# LED_adapt.net
KiCad netlist of a schematic drawn in Altium Designer
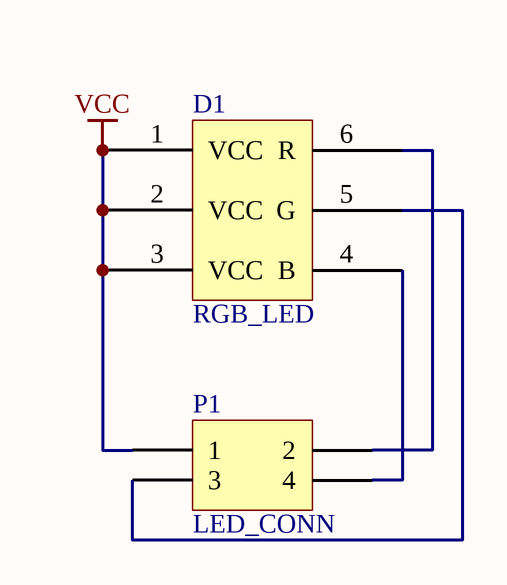
[diagram p0: LED_adapt.SchDoc]

(export (version "E")
  (design (tool "Eeschema 10.0.6"))
  (components
    (comp (ref "D1") (value "RGB_LED") (footprint "CREE_LED") (libsource (lib "mrone") (part "CREE_LED")))
    (comp (ref "P1")
      (value "LED_CONN")
      (footprint "HDR2X2")
      (description "Header, 2-Pin, Dual row")
      (fields (field (name "PUBLISHER") "Altium Limited"))
      (libsource (lib "Miscellaneous Connectors") (part "Header 2X2"))
    )
  )
  (nets
    (net (code "1") (name "Net-(D1-B)") (class "Default")
      (node (ref "D1") (pin "4") (pinfunction "B_4") (pintype "passive"))
      (node (ref "P1") (pin "4") (pinfunction "4_4") (pintype "passive"))
    )
    (net (code "2") (name "Net-(D1-G)") (class "Default")
      (node (ref "D1") (pin "5") (pinfunction "G_5") (pintype "passive"))
      (node (ref "P1") (pin "3") (pinfunction "3_3") (pintype "passive"))
    )
    (net (code "3") (name "Net-(D1-R)") (class "Default")
      (node (ref "D1") (pin "6") (pinfunction "R_6") (pintype "passive"))
      (node (ref "P1") (pin "2") (pinfunction "2_2") (pintype "passive"))
    )
    (net (code "4") (name "VCC") (class "Default")
      (node (ref "D1") (pin "1") (pinfunction "VCC_1") (pintype "passive"))
      (node (ref "D1") (pin "2") (pinfunction "VCC_2") (pintype "passive"))
      (node (ref "D1") (pin "3") (pinfunction "VCC_3") (pintype "passive"))
      (node (ref "P1") (pin "1") (pinfunction "1_1") (pintype "passive"))
    )
  )
)
